# Sheet2.net
KiCad netlist of a schematic drawn in Altium Designer
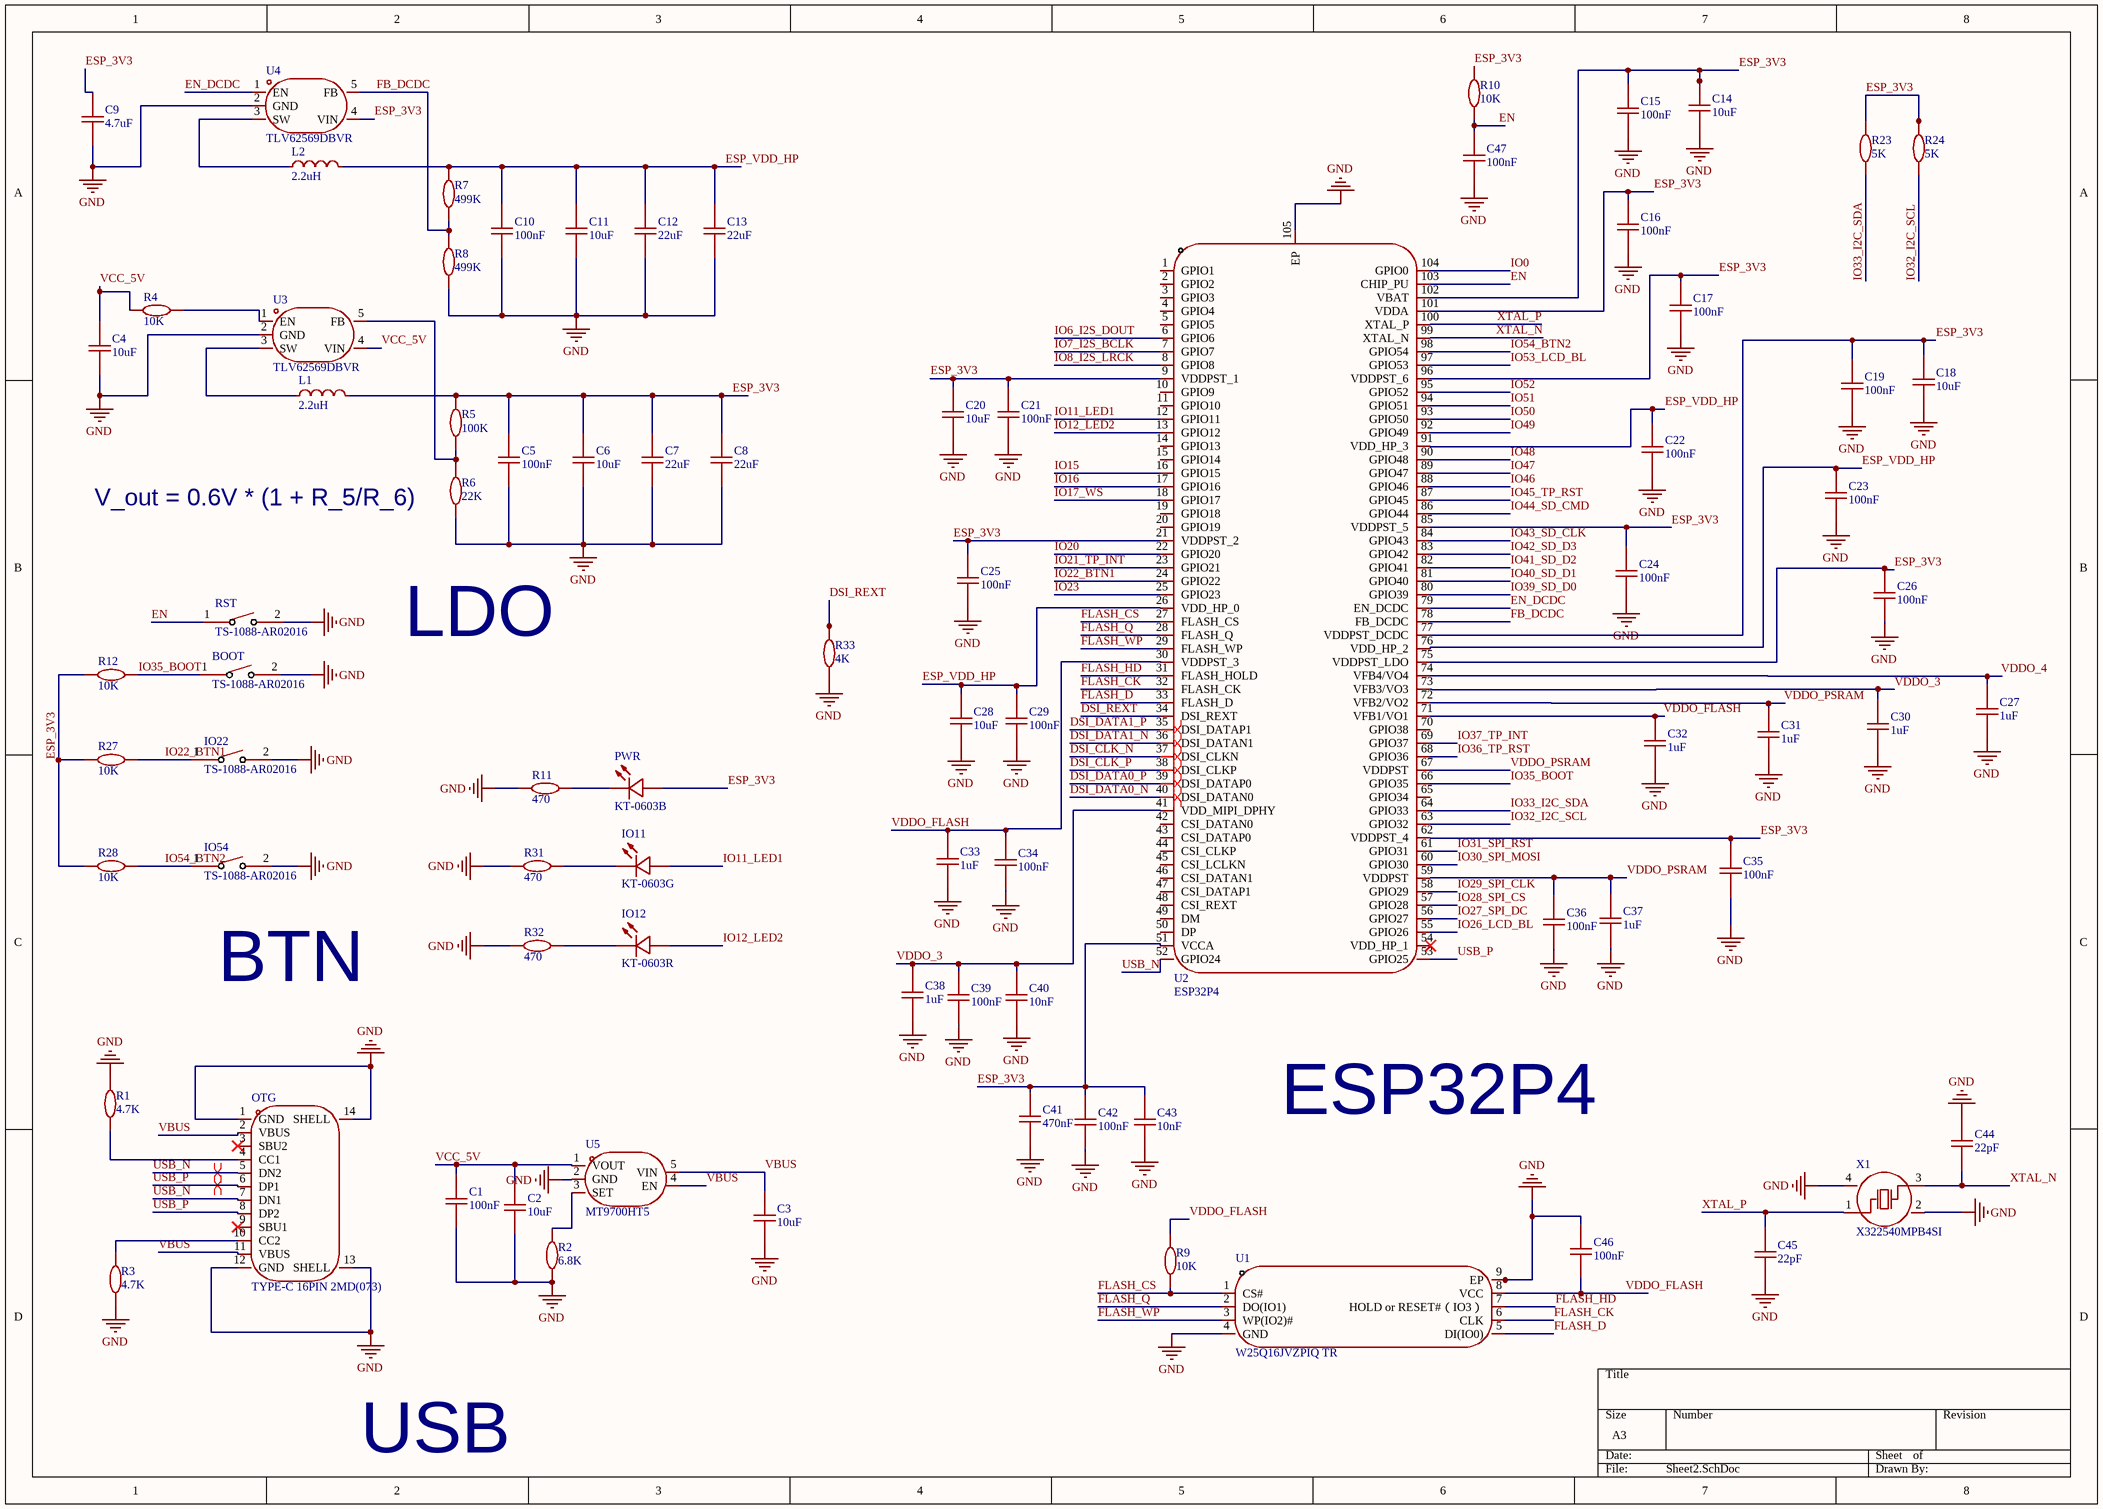
[diagram p0: Sheet2.SchDoc]

(export (version "E")
  (design (tool "Eeschema 10.0.6"))
  (components
    (comp (ref "BOOT")
      (value "TS-1088-AR02016")
      (footprint "SW-SMD_L3.9-W3.0-P4.45")
      (libsource (lib "Switch") (part "TS-1088-AR02016"))
    )
    (comp (ref "C1") (value "100nF") (footprint "C0402") (libsource (lib "RLC") (part "C0402")))
    (comp (ref "C2") (value "10uF") (footprint "C0603") (libsource (lib "RLC") (part "C0603")))
    (comp (ref "C3") (value "10uF") (footprint "C0603") (libsource (lib "RLC") (part "C0603")))
    (comp (ref "C4") (value "10uF") (footprint "C0603") (libsource (lib "RLC") (part "C0603")))
    (comp (ref "C5") (value "100nF") (footprint "C0402") (libsource (lib "RLC") (part "C0402")))
    (comp (ref "C6") (value "10uF") (footprint "C0603") (libsource (lib "RLC") (part "C0603")))
    (comp (ref "C7") (value "22uF") (footprint "C0603") (libsource (lib "RLC") (part "C0603")))
    (comp (ref "C8") (value "22uF") (footprint "C0603") (libsource (lib "RLC") (part "C0603")))
    (comp (ref "C9") (value "4.7uF") (footprint "C0603") (libsource (lib "RLC") (part "C0603")))
    (comp (ref "C10") (value "100nF") (footprint "C0402") (libsource (lib "RLC") (part "C0402")))
    (comp (ref "C11") (value "10uF") (footprint "C0603") (libsource (lib "RLC") (part "C0603")))
    (comp (ref "C12") (value "22uF") (footprint "C0603") (libsource (lib "RLC") (part "C0603")))
    (comp (ref "C13") (value "22uF") (footprint "C0603") (libsource (lib "RLC") (part "C0603")))
    (comp (ref "C14") (value "10uF") (footprint "C0603") (libsource (lib "RLC") (part "C0603")))
    (comp (ref "C15") (value "100nF") (footprint "C0402") (libsource (lib "RLC") (part "C0402")))
    (comp (ref "C16") (value "100nF") (footprint "C0402") (libsource (lib "RLC") (part "C0402")))
    (comp (ref "C17") (value "100nF") (footprint "C0402") (libsource (lib "RLC") (part "C0402")))
    (comp (ref "C18") (value "10uF") (footprint "C0603") (libsource (lib "RLC") (part "C0603")))
    (comp (ref "C19") (value "100nF") (footprint "C0402") (libsource (lib "RLC") (part "C0402")))
    (comp (ref "C20") (value "10uF") (footprint "C0603") (libsource (lib "RLC") (part "C0603")))
    (comp (ref "C21") (value "100nF") (footprint "C0402") (libsource (lib "RLC") (part "C0402")))
    (comp (ref "C22") (value "100nF") (footprint "C0402") (libsource (lib "RLC") (part "C0402")))
    (comp (ref "C23") (value "100nF") (footprint "C0402") (libsource (lib "RLC") (part "C0402")))
    (comp (ref "C24") (value "100nF") (footprint "C0402") (libsource (lib "RLC") (part "C0402")))
    (comp (ref "C25") (value "100nF") (footprint "C0402") (libsource (lib "RLC") (part "C0402")))
    (comp (ref "C26") (value "100nF") (footprint "C0402") (libsource (lib "RLC") (part "C0402")))
    (comp (ref "C27") (value "1uF") (footprint "C0402") (libsource (lib "RLC") (part "C0402")))
    (comp (ref "C28") (value "10uF") (footprint "C0603") (libsource (lib "RLC") (part "C0603")))
    (comp (ref "C29") (value "100nF") (footprint "C0402") (libsource (lib "RLC") (part "C0402")))
    (comp (ref "C30") (value "1uF") (footprint "C0402") (libsource (lib "RLC") (part "C0402")))
    (comp (ref "C31") (value "1uF") (footprint "C0402") (libsource (lib "RLC") (part "C0402")))
    (comp (ref "C32") (value "1uF") (footprint "C0402") (libsource (lib "RLC") (part "C0402")))
    (comp (ref "C33") (value "1uF") (footprint "C0402") (libsource (lib "RLC") (part "C0402")))
    (comp (ref "C34") (value "100nF") (footprint "C0402") (libsource (lib "RLC") (part "C0402")))
    (comp (ref "C35") (value "100nF") (footprint "C0402") (libsource (lib "RLC") (part "C0402")))
    (comp (ref "C36") (value "100nF") (footprint "C0402") (libsource (lib "RLC") (part "C0402")))
    (comp (ref "C37") (value "1uF") (footprint "C0402") (libsource (lib "RLC") (part "C0402")))
    (comp (ref "C38") (value "1uF") (footprint "C0402") (libsource (lib "RLC") (part "C0402")))
    (comp (ref "C39") (value "100nF") (footprint "C0402") (libsource (lib "RLC") (part "C0402")))
    (comp (ref "C40") (value "10nF") (footprint "C0402") (libsource (lib "RLC") (part "C0402")))
    (comp (ref "C41") (value "470nF") (footprint "C0402") (libsource (lib "RLC") (part "C0402")))
    (comp (ref "C42") (value "100nF") (footprint "C0402") (libsource (lib "RLC") (part "C0402")))
    (comp (ref "C43") (value "10nF") (footprint "C0402") (libsource (lib "RLC") (part "C0402")))
    (comp (ref "C44") (value "22pF") (footprint "C0402") (libsource (lib "RLC") (part "C0402")))
    (comp (ref "C45") (value "22pF") (footprint "C0402") (libsource (lib "RLC") (part "C0402")))
    (comp (ref "C46") (value "100nF") (footprint "C0402") (libsource (lib "RLC") (part "C0402")))
    (comp (ref "C47") (value "100nF") (footprint "C0402") (libsource (lib "RLC") (part "C0402")))
    (comp (ref "IO11") (value "KT-0603G") (footprint "LED0603-GR") (libsource (lib "LED") (part "KT-0603G")))
    (comp (ref "IO12") (value "KT-0603R") (footprint "LED0603-RD") (libsource (lib "LED") (part "KT-0603R")))
    (comp (ref "IO22")
      (value "TS-1088-AR02016")
      (footprint "SW-SMD_L3.9-W3.0-P4.45")
      (libsource (lib "Switch") (part "TS-1088-AR02016"))
    )
    (comp (ref "IO54")
      (value "TS-1088-AR02016")
      (footprint "SW-SMD_L3.9-W3.0-P4.45")
      (libsource (lib "Switch") (part "TS-1088-AR02016"))
    )
    (comp (ref "L1") (value "2.2uH") (footprint "L0402-SMD") (libsource (lib "RLC") (part "L0402-SMD")))
    (comp (ref "L2") (value "2.2uH") (footprint "L0402-SMD") (libsource (lib "RLC") (part "L0402-SMD")))
    (comp (ref "OTG")
      (value "TYPE-C 16PIN 2MD(073)")
      (footprint "USB-C-SMD_TYPE-C-6PIN-2MD-073")
      (libsource (lib "Connector") (part "TYPE-C 16PIN 2MD(073)"))
    )
    (comp (ref "PWR") (value "KT-0603B") (footprint "LED0603-BL") (libsource (lib "LED") (part "KT-0603B")))
    (comp (ref "R1") (value "4.7K") (footprint "R0402") (libsource (lib "RLC") (part "R0402")))
    (comp (ref "R2") (value "6.8K") (footprint "R0402") (libsource (lib "RLC") (part "R0402")))
    (comp (ref "R3") (value "4.7K") (footprint "R0402") (libsource (lib "RLC") (part "R0402")))
    (comp (ref "R4") (value "10K") (footprint "R0402") (libsource (lib "RLC") (part "R0402")))
    (comp (ref "R5") (value "100K") (footprint "R0402") (libsource (lib "RLC") (part "R0402")))
    (comp (ref "R6") (value "22K") (footprint "R0402") (libsource (lib "RLC") (part "R0402")))
    (comp (ref "R7") (value "499K") (footprint "R0402") (libsource (lib "RLC") (part "R0402")))
    (comp (ref "R8") (value "499K") (footprint "R0402") (libsource (lib "RLC") (part "R0402")))
    (comp (ref "R9") (value "10K") (footprint "R0402") (libsource (lib "RLC") (part "R0402")))
    (comp (ref "R10") (value "10K") (footprint "R0402") (libsource (lib "RLC") (part "R0402")))
    (comp (ref "R11") (value "470") (footprint "R0402") (libsource (lib "RLC") (part "R0402")))
    (comp (ref "R12") (value "10K") (footprint "R0402") (libsource (lib "RLC") (part "R0402")))
    (comp (ref "R23") (value "5K") (footprint "R0402") (libsource (lib "RLC") (part "R0402")))
    (comp (ref "R24") (value "5K") (footprint "R0402") (libsource (lib "RLC") (part "R0402")))
    (comp (ref "R27") (value "10K") (footprint "R0402") (libsource (lib "RLC") (part "R0402")))
    (comp (ref "R28") (value "10K") (footprint "R0402") (libsource (lib "RLC") (part "R0402")))
    (comp (ref "R31") (value "470") (footprint "R0402") (libsource (lib "RLC") (part "R0402")))
    (comp (ref "R32") (value "470") (footprint "R0402") (libsource (lib "RLC") (part "R0402")))
    (comp (ref "R33") (value "4K") (footprint "R0402") (libsource (lib "RLC") (part "R0402")))
    (comp (ref "RST")
      (value "TS-1088-AR02016")
      (footprint "SW-SMD_L3.9-W3.0-P4.45")
      (libsource (lib "Switch") (part "TS-1088-AR02016"))
    )
    (comp (ref "U1")
      (value "W25Q16JVZPIQ TR")
      (footprint "WSON-8_L6.0-W5.0-P1.27-BL-EP")
      (libsource (lib "IC") (part "W25Q16JVZPIQ TR"))
    )
    (comp (ref "U2")
      (value "ESP32P4")
      (footprint "QFN-104_L10.0-W10.0-P0.35-TL-EP7.5")
      (libsource (lib "IC") (part "ESP32P4"))
    )
    (comp (ref "U3")
      (value "TLV62569DBVR")
      (footprint "SOT-23-5_L3.0-W1.7-P0.95-LS2.8-BR")
      (libsource (lib "LDO") (part "TLV62569DBVR"))
    )
    (comp (ref "U4")
      (value "TLV62569DBVR")
      (footprint "SOT-23-5_L3.0-W1.7-P0.95-LS2.8-BR")
      (libsource (lib "LDO") (part "TLV62569DBVR"))
    )
    (comp (ref "U5")
      (value "MT9700HT5")
      (footprint "SOT-23-5_L3.0-W1.7-P0.95-LS2.8-BL")
      (libsource (lib "IC") (part "MT9700HT5"))
    )
    (comp (ref "X1")
      (value "X322540MPB4SI")
      (footprint "OSC-SMD_4P-L3.2-W2.5-BL_SIT8008BI")
      (libsource (lib "OSC") (part "X322540MPB4SI"))
    )
  )
  (nets
    (net (code "1") (name "/DSI_CLK_N") (class "Default")
      (node (ref "U2") (pin "37") (pinfunction "DSI_CLKN_37") (pintype "passive"))
    )
    (net (code "2") (name "/DSI_CLK_P") (class "Default")
      (node (ref "U2") (pin "38") (pinfunction "DSI_CLKP_38") (pintype "passive"))
    )
    (net (code "3") (name "/DSI_DATA0_N") (class "Default")
      (node (ref "U2") (pin "40") (pinfunction "DSI_DATAN0_40") (pintype "passive"))
    )
    (net (code "4") (name "/DSI_DATA0_P") (class "Default")
      (node (ref "U2") (pin "39") (pinfunction "DSI_DATAP0_39") (pintype "passive"))
    )
    (net (code "5") (name "/DSI_DATA1_N") (class "Default")
      (node (ref "U2") (pin "36") (pinfunction "DSI_DATAN1_36") (pintype "passive"))
    )
    (net (code "6") (name "/DSI_DATA1_P") (class "Default")
      (node (ref "U2") (pin "35") (pinfunction "DSI_DATAP1_35") (pintype "passive"))
    )
    (net (code "7") (name "/DSI_REXT") (class "Default")
      (node (ref "R33") (pin "1") (pinfunction "1_1") (pintype "passive"))
      (node (ref "U2") (pin "34") (pinfunction "DSI_REXT_34") (pintype "passive"))
    )
    (net (code "8") (name "/EN") (class "Default")
      (node (ref "C47") (pin "2") (pinfunction "2_2") (pintype "passive"))
      (node (ref "R10") (pin "1") (pinfunction "1_1") (pintype "passive"))
      (node (ref "RST") (pin "1") (pinfunction "1_1") (pintype "passive"))
      (node (ref "U2") (pin "103") (pinfunction "CHIP_PU_103") (pintype "passive"))
    )
    (net (code "9") (name "/EN_DCDC") (class "Default")
      (node (ref "U2") (pin "79") (pinfunction "EN_DCDC_79") (pintype "passive"))
      (node (ref "U4") (pin "1") (pinfunction "EN_1") (pintype "passive"))
    )
    (net (code "10") (name "/ESP_3V3") (class "Default")
      (node (ref "C14") (pin "2") (pinfunction "2_2") (pintype "passive"))
      (node (ref "C15") (pin "2") (pinfunction "2_2") (pintype "passive"))
      (node (ref "C16") (pin "2") (pinfunction "2_2") (pintype "passive"))
      (node (ref "C17") (pin "2") (pinfunction "2_2") (pintype "passive"))
      (node (ref "C18") (pin "2") (pinfunction "2_2") (pintype "passive"))
      (node (ref "C19") (pin "2") (pinfunction "2_2") (pintype "passive"))
      (node (ref "C20") (pin "2") (pinfunction "2_2") (pintype "passive"))
      (node (ref "C21") (pin "2") (pinfunction "2_2") (pintype "passive"))
      (node (ref "C24") (pin "2") (pinfunction "2_2") (pintype "passive"))
      (node (ref "C25") (pin "2") (pinfunction "2_2") (pintype "passive"))
      (node (ref "C26") (pin "2") (pinfunction "2_2") (pintype "passive"))
      (node (ref "C35") (pin "2") (pinfunction "2_2") (pintype "passive"))
      (node (ref "C41") (pin "2") (pinfunction "2_2") (pintype "passive"))
      (node (ref "C42") (pin "2") (pinfunction "2_2") (pintype "passive"))
      (node (ref "C43") (pin "2") (pinfunction "2_2") (pintype "passive"))
      (node (ref "C5") (pin "2") (pinfunction "2_2") (pintype "passive"))
      (node (ref "C6") (pin "2") (pinfunction "2_2") (pintype "passive"))
      (node (ref "C7") (pin "2") (pinfunction "2_2") (pintype "passive"))
      (node (ref "C8") (pin "2") (pinfunction "2_2") (pintype "passive"))
      (node (ref "C9") (pin "1") (pinfunction "1_1") (pintype "passive"))
      (node (ref "L1") (pin "2") (pinfunction "2_2") (pintype "passive"))
      (node (ref "PWR") (pin "2") (pinfunction "A_2") (pintype "passive"))
      (node (ref "R10") (pin "2") (pinfunction "2_2") (pintype "passive"))
      (node (ref "R12") (pin "2") (pinfunction "2_2") (pintype "passive"))
      (node (ref "R23") (pin "2") (pinfunction "2_2") (pintype "passive"))
      (node (ref "R24") (pin "2") (pinfunction "2_2") (pintype "passive"))
      (node (ref "R27") (pin "2") (pinfunction "2_2") (pintype "passive"))
      (node (ref "R28") (pin "2") (pinfunction "2_2") (pintype "passive"))
      (node (ref "R5") (pin "2") (pinfunction "2_2") (pintype "passive"))
      (node (ref "U2") (pin "101") (pinfunction "VDDA_101") (pintype "passive"))
      (node (ref "U2") (pin "102") (pinfunction "VBAT_102") (pintype "passive"))
      (node (ref "U2") (pin "21") (pinfunction "VDDPST_2_21") (pintype "passive"))
      (node (ref "U2") (pin "51") (pinfunction "VCCA_51") (pintype "passive"))
      (node (ref "U2") (pin "62") (pinfunction "VDDPST_4_62") (pintype "passive"))
      (node (ref "U2") (pin "75") (pinfunction "VDDPST_LDO_75") (pintype "passive"))
      (node (ref "U2") (pin "77") (pinfunction "VDDPST_DCDC_77") (pintype "passive"))
      (node (ref "U2") (pin "85") (pinfunction "VDDPST_5_85") (pintype "passive"))
      (node (ref "U2") (pin "9") (pinfunction "VDDPST_1_9") (pintype "passive"))
      (node (ref "U2") (pin "96") (pinfunction "VDDPST_6_96") (pintype "passive"))
      (node (ref "U4") (pin "4") (pinfunction "VIN_4") (pintype "passive"))
    )
    (net (code "11") (name "/ESP_VDD_HP") (class "Default")
      (node (ref "C10") (pin "2") (pinfunction "2_2") (pintype "passive"))
      (node (ref "C11") (pin "2") (pinfunction "2_2") (pintype "passive"))
      (node (ref "C12") (pin "2") (pinfunction "2_2") (pintype "passive"))
      (node (ref "C13") (pin "2") (pinfunction "2_2") (pintype "passive"))
      (node (ref "C22") (pin "2") (pinfunction "2_2") (pintype "passive"))
      (node (ref "C23") (pin "2") (pinfunction "2_2") (pintype "passive"))
      (node (ref "C28") (pin "2") (pinfunction "2_2") (pintype "passive"))
      (node (ref "C29") (pin "2") (pinfunction "2_2") (pintype "passive"))
      (node (ref "L2") (pin "2") (pinfunction "2_2") (pintype "passive"))
      (node (ref "R7") (pin "2") (pinfunction "2_2") (pintype "passive"))
      (node (ref "U2") (pin "26") (pinfunction "VDD_HP_0_26") (pintype "passive"))
      (node (ref "U2") (pin "76") (pinfunction "VDD_HP_2_76") (pintype "passive"))
      (node (ref "U2") (pin "91") (pinfunction "VDD_HP_3_91") (pintype "passive"))
    )
    (net (code "12") (name "/FB_DCDC") (class "Default")
      (node (ref "R7") (pin "1") (pinfunction "1_1") (pintype "passive"))
      (node (ref "R8") (pin "2") (pinfunction "2_2") (pintype "passive"))
      (node (ref "U2") (pin "78") (pinfunction "FB_DCDC_78") (pintype "passive"))
      (node (ref "U4") (pin "5") (pinfunction "FB_5") (pintype "passive"))
    )
    (net (code "13") (name "/FLASH_CK") (class "Default")
      (node (ref "U1") (pin "6") (pinfunction "CLK_6") (pintype "passive"))
      (node (ref "U2") (pin "32") (pinfunction "FLASH_CK_32") (pintype "passive"))
    )
    (net (code "14") (name "/FLASH_CS") (class "Default")
      (node (ref "R9") (pin "1") (pinfunction "1_1") (pintype "passive"))
      (node (ref "U1") (pin "1") (pinfunction "CS#_1") (pintype "passive"))
      (node (ref "U2") (pin "27") (pinfunction "FLASH_CS_27") (pintype "passive"))
    )
    (net (code "15") (name "/FLASH_D") (class "Default")
      (node (ref "U1") (pin "5") (pinfunction "DI(IO0)_5") (pintype "passive"))
      (node (ref "U2") (pin "33") (pinfunction "FLASH_D_33") (pintype "passive"))
    )
    (net (code "16") (name "/FLASH_HD") (class "Default")
      (node (ref "U1") (pin "7") (pinfunction "HOLD_or_RESET#（IO3）_7") (pintype "passive"))
      (node (ref "U2") (pin "31") (pinfunction "FLASH_HOLD_31") (pintype "passive"))
    )
    (net (code "17") (name "/FLASH_Q") (class "Default")
      (node (ref "U1") (pin "2") (pinfunction "DO(IO1)_2") (pintype "passive"))
      (node (ref "U2") (pin "28") (pinfunction "FLASH_Q_28") (pintype "passive"))
    )
    (net (code "18") (name "/FLASH_WP") (class "Default")
      (node (ref "U1") (pin "3") (pinfunction "WP(IO2)#_3") (pintype "passive"))
      (node (ref "U2") (pin "29") (pinfunction "FLASH_WP_29") (pintype "passive"))
    )
    (net (code "19") (name "/IO0") (class "Default")
      (node (ref "U2") (pin "104") (pinfunction "GPIO0_104") (pintype "passive"))
    )
    (net (code "20") (name "/IO6_I2S_DOUT") (class "Default")
      (node (ref "U2") (pin "6") (pinfunction "GPIO6_6") (pintype "passive"))
    )
    (net (code "21") (name "/IO7_I2S_BCLK") (class "Default")
      (node (ref "U2") (pin "7") (pinfunction "GPIO7_7") (pintype "passive"))
    )
    (net (code "22") (name "/IO8_I2S_LRCK") (class "Default")
      (node (ref "U2") (pin "8") (pinfunction "GPIO8_8") (pintype "passive"))
    )
    (net (code "23") (name "/IO11_LED1") (class "Default")
      (node (ref "IO11") (pin "2") (pinfunction "A_2") (pintype "passive"))
      (node (ref "U2") (pin "12") (pinfunction "GPIO11_12") (pintype "passive"))
    )
    (net (code "24") (name "/IO12_LED2") (class "Default")
      (node (ref "IO12") (pin "2") (pinfunction "A_2") (pintype "passive"))
      (node (ref "U2") (pin "13") (pinfunction "GPIO12_13") (pintype "passive"))
    )
    (net (code "25") (name "/IO15") (class "Default")
      (node (ref "U2") (pin "16") (pinfunction "GPIO15_16") (pintype "passive"))
    )
    (net (code "26") (name "/IO16") (class "Default")
      (node (ref "U2") (pin "17") (pinfunction "GPIO16_17") (pintype "passive"))
    )
    (net (code "27") (name "/IO17_WS") (class "Default")
      (node (ref "U2") (pin "18") (pinfunction "GPIO17_18") (pintype "passive"))
    )
    (net (code "28") (name "/IO20") (class "Default")
      (node (ref "U2") (pin "22") (pinfunction "GPIO20_22") (pintype "passive"))
    )
    (net (code "29") (name "/IO21_TP_INT") (class "Default")
      (node (ref "U2") (pin "23") (pinfunction "GPIO21_23") (pintype "passive"))
    )
    (net (code "30") (name "/IO22_BTN1") (class "Default")
      (node (ref "IO22") (pin "1") (pinfunction "1_1") (pintype "passive"))
      (node (ref "R27") (pin "1") (pinfunction "1_1") (pintype "passive"))
      (node (ref "U2") (pin "24") (pinfunction "GPIO22_24") (pintype "passive"))
    )
    (net (code "31") (name "/IO23") (class "Default")
      (node (ref "U2") (pin "25") (pinfunction "GPIO23_25") (pintype "passive"))
    )
    (net (code "32") (name "/IO26_LCD_BL") (class "Default")
      (node (ref "U2") (pin "55") (pinfunction "GPIO26_55") (pintype "passive"))
    )
    (net (code "33") (name "/IO27_SPI_DC") (class "Default")
      (node (ref "U2") (pin "56") (pinfunction "GPIO27_56") (pintype "passive"))
    )
    (net (code "34") (name "/IO28_SPI_CS") (class "Default")
      (node (ref "U2") (pin "57") (pinfunction "GPIO28_57") (pintype "passive"))
    )
    (net (code "35") (name "/IO29_SPI_CLK") (class "Default")
      (node (ref "U2") (pin "58") (pinfunction "GPIO29_58") (pintype "passive"))
    )
    (net (code "36") (name "/IO30_SPI_MOSI") (class "Default")
      (node (ref "U2") (pin "60") (pinfunction "GPIO30_60") (pintype "passive"))
    )
    (net (code "37") (name "/IO31_SPI_RST") (class "Default")
      (node (ref "U2") (pin "61") (pinfunction "GPIO31_61") (pintype "passive"))
    )
    (net (code "38") (name "/IO32_I2C_SCL") (class "Default")
      (node (ref "R24") (pin "1") (pinfunction "1_1") (pintype "passive"))
      (node (ref "U2") (pin "63") (pinfunction "GPIO32_63") (pintype "passive"))
    )
    (net (code "39") (name "/IO33_I2C_SDA") (class "Default")
      (node (ref "R23") (pin "1") (pinfunction "1_1") (pintype "passive"))
      (node (ref "U2") (pin "64") (pinfunction "GPIO33_64") (pintype "passive"))
    )
    (net (code "40") (name "/IO35_BOOT") (class "Default")
      (node (ref "BOOT") (pin "1") (pinfunction "1_1") (pintype "passive"))
      (node (ref "R12") (pin "1") (pinfunction "1_1") (pintype "passive"))
      (node (ref "U2") (pin "66") (pinfunction "GPIO35_66") (pintype "passive"))
    )
    (net (code "41") (name "/IO36_TP_RST") (class "Default")
      (node (ref "U2") (pin "68") (pinfunction "GPIO36_68") (pintype "passive"))
    )
    (net (code "42") (name "/IO37_TP_INT") (class "Default")
      (node (ref "U2") (pin "69") (pinfunction "GPIO37_69") (pintype "passive"))
    )
    (net (code "43") (name "/IO39_SD_D0") (class "Default")
      (node (ref "U2") (pin "80") (pinfunction "GPIO39_80") (pintype "passive"))
    )
    (net (code "44") (name "/IO40_SD_D1") (class "Default")
      (node (ref "U2") (pin "81") (pinfunction "GPIO40_81") (pintype "passive"))
    )
    (net (code "45") (name "/IO41_SD_D2") (class "Default")
      (node (ref "U2") (pin "82") (pinfunction "GPIO41_82") (pintype "passive"))
    )
    (net (code "46") (name "/IO42_SD_D3") (class "Default")
      (node (ref "U2") (pin "83") (pinfunction "GPIO42_83") (pintype "passive"))
    )
    (net (code "47") (name "/IO43_SD_CLK") (class "Default")
      (node (ref "U2") (pin "84") (pinfunction "GPIO43_84") (pintype "passive"))
    )
    (net (code "48") (name "/IO44_SD_CMD") (class "Default")
      (node (ref "U2") (pin "86") (pinfunction "GPIO44_86") (pintype "passive"))
    )
    (net (code "49") (name "/IO45_TP_RST") (class "Default")
      (node (ref "U2") (pin "87") (pinfunction "GPIO45_87") (pintype "passive"))
    )
    (net (code "50") (name "/IO46") (class "Default")
      (node (ref "U2") (pin "88") (pinfunction "GPIO46_88") (pintype "passive"))
    )
    (net (code "51") (name "/IO47") (class "Default")
      (node (ref "U2") (pin "89") (pinfunction "GPIO47_89") (pintype "passive"))
    )
    (net (code "52") (name "/IO48") (class "Default")
      (node (ref "U2") (pin "90") (pinfunction "GPIO48_90") (pintype "passive"))
    )
    (net (code "53") (name "/IO49") (class "Default")
      (node (ref "U2") (pin "92") (pinfunction "GPIO49_92") (pintype "passive"))
    )
    (net (code "54") (name "/IO50") (class "Default")
      (node (ref "U2") (pin "93") (pinfunction "GPIO50_93") (pintype "passive"))
    )
    (net (code "55") (name "/IO51") (class "Default")
      (node (ref "U2") (pin "94") (pinfunction "GPIO51_94") (pintype "passive"))
    )
    (net (code "56") (name "/IO52") (class "Default")
      (node (ref "U2") (pin "95") (pinfunction "GPIO52_95") (pintype "passive"))
    )
    (net (code "57") (name "/IO53_LCD_BL") (class "Default")
      (node (ref "U2") (pin "97") (pinfunction "GPIO53_97") (pintype "passive"))
    )
    (net (code "58") (name "/IO54_BTN2") (class "Default")
      (node (ref "IO54") (pin "1") (pinfunction "1_1") (pintype "passive"))
      (node (ref "R28") (pin "1") (pinfunction "1_1") (pintype "passive"))
      (node (ref "U2") (pin "98") (pinfunction "GPIO54_98") (pintype "passive"))
    )
    (net (code "59") (name "/USB_N") (class "Default")
      (node (ref "OTG") (pin "5") (pinfunction "DN2_5") (pintype "passive"))
      (node (ref "OTG") (pin "7") (pinfunction "DN1_7") (pintype "passive"))
      (node (ref "U2") (pin "52") (pinfunction "GPIO24_52") (pintype "passive"))
    )
    (net (code "60") (name "/USB_P") (class "Default")
      (node (ref "OTG") (pin "6") (pinfunction "DP1_6") (pintype "passive"))
      (node (ref "OTG") (pin "8") (pinfunction "DP2_8") (pintype "passive"))
      (node (ref "U2") (pin "53") (pinfunction "GPIO25_53") (pintype "passive"))
    )
    (net (code "61") (name "/VBUS") (class "Default")
      (node (ref "C3") (pin "1") (pinfunction "1_1") (pintype "passive"))
      (node (ref "OTG") (pin "11") (pinfunction "VBUS_11") (pintype "passive"))
      (node (ref "OTG") (pin "2") (pinfunction "VBUS_2") (pintype "passive"))
      (node (ref "U5") (pin "4") (pinfunction "EN_4") (pintype "passive"))
      (node (ref "U5") (pin "5") (pinfunction "VIN_5") (pintype "passive"))
    )
    (net (code "62") (name "/VCC_5V") (class "Default")
      (node (ref "C1") (pin "2") (pinfunction "2_2") (pintype "passive"))
      (node (ref "C2") (pin "1") (pinfunction "1_1") (pintype "passive"))
      (node (ref "C4") (pin "1") (pinfunction "1_1") (pintype "passive"))
      (node (ref "R4") (pin "2") (pinfunction "2_2") (pintype "passive"))
      (node (ref "U3") (pin "4") (pinfunction "VIN_4") (pintype "passive"))
      (node (ref "U5") (pin "1") (pinfunction "VOUT_1") (pintype "passive"))
    )
    (net (code "63") (name "/VDDO_3") (class "Default")
      (node (ref "C30") (pin "2") (pinfunction "2_2") (pintype "passive"))
      (node (ref "C38") (pin "2") (pinfunction "2_2") (pintype "passive"))
      (node (ref "C39") (pin "2") (pinfunction "2_2") (pintype "passive"))
      (node (ref "C40") (pin "2") (pinfunction "2_2") (pintype "passive"))
      (node (ref "U2") (pin "41") (pinfunction "VDD_MIPI_DPHY_41") (pintype "passive"))
      (node (ref "U2") (pin "73") (pinfunction "VFB3/VO3_73") (pintype "passive"))
    )
    (net (code "64") (name "/VDDO_4") (class "Default")
      (node (ref "C27") (pin "2") (pinfunction "2_2") (pintype "passive"))
      (node (ref "U2") (pin "74") (pinfunction "VFB4/VO4_74") (pintype "passive"))
    )
    (net (code "65") (name "/VDDO_FLASH") (class "Default")
      (node (ref "C32") (pin "2") (pinfunction "2_2") (pintype "passive"))
      (node (ref "C33") (pin "2") (pinfunction "2_2") (pintype "passive"))
      (node (ref "C34") (pin "2") (pinfunction "2_2") (pintype "passive"))
      (node (ref "C46") (pin "1") (pinfunction "1_1") (pintype "passive"))
      (node (ref "R9") (pin "2") (pinfunction "2_2") (pintype "passive"))
      (node (ref "U1") (pin "8") (pinfunction "VCC_8") (pintype "passive"))
      (node (ref "U2") (pin "30") (pinfunction "VDDPST_3_30") (pintype "passive"))
      (node (ref "U2") (pin "71") (pinfunction "VFB1/VO1_71") (pintype "passive"))
    )
    (net (code "66") (name "/VDDO_PSRAM") (class "Default")
      (node (ref "C31") (pin "2") (pinfunction "2_2") (pintype "passive"))
      (node (ref "C36") (pin "2") (pinfunction "2_2") (pintype "passive"))
      (node (ref "C37") (pin "2") (pinfunction "2_2") (pintype "passive"))
      (node (ref "U2") (pin "59") (pinfunction "VDDPST_59") (pintype "passive"))
      (node (ref "U2") (pin "67") (pinfunction "VDDPST_67") (pintype "passive"))
      (node (ref "U2") (pin "72") (pinfunction "VFB2/VO2_72") (pintype "passive"))
    )
    (net (code "67") (name "/XTAL_N") (class "Default")
      (node (ref "C44") (pin "1") (pinfunction "1_1") (pintype "passive"))
      (node (ref "U2") (pin "99") (pinfunction "XTAL_N_99") (pintype "passive"))
      (node (ref "X1") (pin "3") (pinfunction "OSC2_3") (pintype "passive"))
    )
    (net (code "68") (name "/XTAL_P") (class "Default")
      (node (ref "C45") (pin "2") (pinfunction "2_2") (pintype "passive"))
      (node (ref "U2") (pin "100") (pinfunction "XTAL_P_100") (pintype "passive"))
      (node (ref "X1") (pin "1") (pinfunction "OSC1_1") (pintype "passive"))
    )
    (net (code "69") (name "GND") (class "Default")
      (node (ref "BOOT") (pin "2") (pinfunction "2_2") (pintype "passive"))
      (node (ref "C1") (pin "1") (pinfunction "1_1") (pintype "passive"))
      (node (ref "C10") (pin "1") (pinfunction "1_1") (pintype "passive"))
      (node (ref "C11") (pin "1") (pinfunction "1_1") (pintype "passive"))
      (node (ref "C12") (pin "1") (pinfunction "1_1") (pintype "passive"))
      (node (ref "C13") (pin "1") (pinfunction "1_1") (pintype "passive"))
      (node (ref "C14") (pin "1") (pinfunction "1_1") (pintype "passive"))
      (node (ref "C15") (pin "1") (pinfunction "1_1") (pintype "passive"))
      (node (ref "C16") (pin "1") (pinfunction "1_1") (pintype "passive"))
      (node (ref "C17") (pin "1") (pinfunction "1_1") (pintype "passive"))
      (node (ref "C18") (pin "1") (pinfunction "1_1") (pintype "passive"))
      (node (ref "C19") (pin "1") (pinfunction "1_1") (pintype "passive"))
      (node (ref "C2") (pin "2") (pinfunction "2_2") (pintype "passive"))
      (node (ref "C20") (pin "1") (pinfunction "1_1") (pintype "passive"))
      (node (ref "C21") (pin "1") (pinfunction "1_1") (pintype "passive"))
      (node (ref "C22") (pin "1") (pinfunction "1_1") (pintype "passive"))
      (node (ref "C23") (pin "1") (pinfunction "1_1") (pintype "passive"))
      (node (ref "C24") (pin "1") (pinfunction "1_1") (pintype "passive"))
      (node (ref "C25") (pin "1") (pinfunction "1_1") (pintype "passive"))
      (node (ref "C26") (pin "1") (pinfunction "1_1") (pintype "passive"))
      (node (ref "C27") (pin "1") (pinfunction "1_1") (pintype "passive"))
      (node (ref "C28") (pin "1") (pinfunction "1_1") (pintype "passive"))
      (node (ref "C29") (pin "1") (pinfunction "1_1") (pintype "passive"))
      (node (ref "C3") (pin "2") (pinfunction "2_2") (pintype "passive"))
      (node (ref "C30") (pin "1") (pinfunction "1_1") (pintype "passive"))
      (node (ref "C31") (pin "1") (pinfunction "1_1") (pintype "passive"))
      (node (ref "C32") (pin "1") (pinfunction "1_1") (pintype "passive"))
      (node (ref "C33") (pin "1") (pinfunction "1_1") (pintype "passive"))
      (node (ref "C34") (pin "1") (pinfunction "1_1") (pintype "passive"))
      (node (ref "C35") (pin "1") (pinfunction "1_1") (pintype "passive"))
      (node (ref "C36") (pin "1") (pinfunction "1_1") (pintype "passive"))
      (node (ref "C37") (pin "1") (pinfunction "1_1") (pintype "passive"))
      (node (ref "C38") (pin "1") (pinfunction "1_1") (pintype "passive"))
      (node (ref "C39") (pin "1") (pinfunction "1_1") (pintype "passive"))
      (node (ref "C4") (pin "2") (pinfunction "2_2") (pintype "passive"))
      (node (ref "C40") (pin "1") (pinfunction "1_1") (pintype "passive"))
      (node (ref "C41") (pin "1") (pinfunction "1_1") (pintype "passive"))
      (node (ref "C42") (pin "1") (pinfunction "1_1") (pintype "passive"))
      (node (ref "C43") (pin "1") (pinfunction "1_1") (pintype "passive"))
      (node (ref "C44") (pin "2") (pinfunction "2_2") (pintype "passive"))
      (node (ref "C45") (pin "1") (pinfunction "1_1") (pintype "passive"))
      (node (ref "C46") (pin "2") (pinfunction "2_2") (pintype "passive"))
      (node (ref "C47") (pin "1") (pinfunction "1_1") (pintype "passive"))
      (node (ref "C5") (pin "1") (pinfunction "1_1") (pintype "passive"))
      (node (ref "C6") (pin "1") (pinfunction "1_1") (pintype "passive"))
      (node (ref "C7") (pin "1") (pinfunction "1_1") (pintype "passive"))
      (node (ref "C8") (pin "1") (pinfunction "1_1") (pintype "passive"))
      (node (ref "C9") (pin "2") (pinfunction "2_2") (pintype "passive"))
      (node (ref "IO22") (pin "2") (pinfunction "2_2") (pintype "passive"))
      (node (ref "IO54") (pin "2") (pinfunction "2_2") (pintype "passive"))
      (node (ref "OTG") (pin "1") (pinfunction "GND_1") (pintype "passive"))
      (node (ref "OTG") (pin "12") (pinfunction "GND_12") (pintype "passive"))
      (node (ref "OTG") (pin "13") (pinfunction "SHELL_13") (pintype "passive"))
      (node (ref "OTG") (pin "14") (pinfunction "SHELL_14") (pintype "passive"))
      (node (ref "R1") (pin "2") (pinfunction "2_2") (pintype "passive"))
      (node (ref "R11") (pin "2") (pinfunction "2_2") (pintype "passive"))
      (node (ref "R2") (pin "2") (pinfunction "2_2") (pintype "passive"))
      (node (ref "R3") (pin "1") (pinfunction "1_1") (pintype "passive"))
      (node (ref "R31") (pin "2") (pinfunction "2_2") (pintype "passive"))
      (node (ref "R32") (pin "2") (pinfunction "2_2") (pintype "passive"))
      (node (ref "R33") (pin "2") (pinfunction "2_2") (pintype "passive"))
      (node (ref "R6") (pin "1") (pinfunction "1_1") (pintype "passive"))
      (node (ref "R8") (pin "1") (pinfunction "1_1") (pintype "passive"))
      (node (ref "RST") (pin "2") (pinfunction "2_2") (pintype "passive"))
      (node (ref "U1") (pin "4") (pinfunction "GND_4") (pintype "passive"))
      (node (ref "U1") (pin "9") (pinfunction "EP_9") (pintype "passive"))
      (node (ref "U2") (pin "105") (pinfunction "EP_105") (pintype "passive"))
      (node (ref "U3") (pin "2") (pinfunction "GND_2") (pintype "passive"))
      (node (ref "U4") (pin "2") (pinfunction "GND_2") (pintype "passive"))
      (node (ref "U5") (pin "2") (pinfunction "GND_2") (pintype "passive"))
      (node (ref "X1") (pin "2") (pinfunction "GND_2") (pintype "passive"))
      (node (ref "X1") (pin "4") (pinfunction "GND_4") (pintype "passive"))
    )
    (net (code "70") (name "Net-(IO11-K)") (class "Default")
      (node (ref "IO11") (pin "1") (pinfunction "K_1") (pintype "passive"))
      (node (ref "R31") (pin "1") (pinfunction "1_1") (pintype "passive"))
    )
    (net (code "71") (name "Net-(IO12-K)") (class "Default")
      (node (ref "IO12") (pin "1") (pinfunction "K_1") (pintype "passive"))
      (node (ref "R32") (pin "1") (pinfunction "1_1") (pintype "passive"))
    )
    (net (code "72") (name "Net-(OTG-CC1)") (class "Default")
      (node (ref "OTG") (pin "4") (pinfunction "CC1_4") (pintype "passive"))
      (node (ref "R1") (pin "1") (pinfunction "1_1") (pintype "passive"))
    )
    (net (code "73") (name "Net-(OTG-CC2)") (class "Default")
      (node (ref "OTG") (pin "10") (pinfunction "CC2_10") (pintype "passive"))
      (node (ref "R3") (pin "2") (pinfunction "2_2") (pintype "passive"))
    )
    (net (code "74") (name "Net-(PWR-K)") (class "Default")
      (node (ref "PWR") (pin "1") (pinfunction "K_1") (pintype "passive"))
      (node (ref "R11") (pin "1") (pinfunction "1_1") (pintype "passive"))
    )
    (net (code "75") (name "Net-(U3-EN)") (class "Default")
      (node (ref "R4") (pin "1") (pinfunction "1_1") (pintype "passive"))
      (node (ref "U3") (pin "1") (pinfunction "EN_1") (pintype "passive"))
    )
    (net (code "76") (name "Net-(U3-FB)") (class "Default")
      (node (ref "R5") (pin "1") (pinfunction "1_1") (pintype "passive"))
      (node (ref "R6") (pin "2") (pinfunction "2_2") (pintype "passive"))
      (node (ref "U3") (pin "5") (pinfunction "FB_5") (pintype "passive"))
    )
    (net (code "77") (name "Net-(U3-SW)") (class "Default")
      (node (ref "L1") (pin "1") (pinfunction "1_1") (pintype "passive"))
      (node (ref "U3") (pin "3") (pinfunction "SW_3") (pintype "passive"))
    )
    (net (code "78") (name "Net-(U4-SW)") (class "Default")
      (node (ref "L2") (pin "1") (pinfunction "1_1") (pintype "passive"))
      (node (ref "U4") (pin "3") (pinfunction "SW_3") (pintype "passive"))
    )
    (net (code "79") (name "Net-(U5-SET)") (class "Default")
      (node (ref "R2") (pin "1") (pinfunction "1_1") (pintype "passive"))
      (node (ref "U5") (pin "3") (pinfunction "SET_3") (pintype "passive"))
    )
    (net (code "80") (name "unconnected-(OTG-SBU1-Pad9)") (class "Default")
      (node (ref "OTG") (pin "9") (pinfunction "SBU1_9") (pintype "passive+no_connect"))
    )
    (net (code "81") (name "unconnected-(OTG-SBU2-Pad3)") (class "Default")
      (node (ref "OTG") (pin "3") (pinfunction "SBU2_3") (pintype "passive+no_connect"))
    )
    (net (code "82") (name "unconnected-(U2-CSI_CLKP-Pad44)") (class "Default")
      (node (ref "U2") (pin "44") (pinfunction "CSI_CLKP_44") (pintype "passive"))
    )
    (net (code "83") (name "unconnected-(U2-CSI_DATAN0-Pad42)") (class "Default")
      (node (ref "U2") (pin "42") (pinfunction "CSI_DATAN0_42") (pintype "passive"))
    )
    (net (code "84") (name "unconnected-(U2-CSI_DATAN1-Pad46)") (class "Default")
      (node (ref "U2") (pin "46") (pinfunction "CSI_DATAN1_46") (pintype "passive"))
    )
    (net (code "85") (name "unconnected-(U2-CSI_DATAP0-Pad43)") (class "Default")
      (node (ref "U2") (pin "43") (pinfunction "CSI_DATAP0_43") (pintype "passive"))
    )
    (net (code "86") (name "unconnected-(U2-CSI_DATAP1-Pad47)") (class "Default")
      (node (ref "U2") (pin "47") (pinfunction "CSI_DATAP1_47") (pintype "passive"))
    )
    (net (code "87") (name "unconnected-(U2-CSI_LCLKN-Pad45)") (class "Default")
      (node (ref "U2") (pin "45") (pinfunction "CSI_LCLKN_45") (pintype "passive"))
    )
    (net (code "88") (name "unconnected-(U2-CSI_REXT-Pad48)") (class "Default")
      (node (ref "U2") (pin "48") (pinfunction "CSI_REXT_48") (pintype "passive"))
    )
    (net (code "89") (name "unconnected-(U2-DM-Pad49)") (class "Default")
      (node (ref "U2") (pin "49") (pinfunction "DM_49") (pintype "passive"))
    )
    (net (code "90") (name "unconnected-(U2-DP-Pad50)") (class "Default")
      (node (ref "U2") (pin "50") (pinfunction "DP_50") (pintype "passive"))
    )
    (net (code "91") (name "unconnected-(U2-GPIO1-Pad1)") (class "Default")
      (node (ref "U2") (pin "1") (pinfunction "GPIO1_1") (pintype "passive"))
    )
    (net (code "92") (name "unconnected-(U2-GPIO2-Pad2)") (class "Default")
      (node (ref "U2") (pin "2") (pinfunction "GPIO2_2") (pintype "passive"))
    )
    (net (code "93") (name "unconnected-(U2-GPIO3-Pad3)") (class "Default")
      (node (ref "U2") (pin "3") (pinfunction "GPIO3_3") (pintype "passive"))
    )
    (net (code "94") (name "unconnected-(U2-GPIO4-Pad4)") (class "Default")
      (node (ref "U2") (pin "4") (pinfunction "GPIO4_4") (pintype "passive"))
    )
    (net (code "95") (name "unconnected-(U2-GPIO5-Pad5)") (class "Default")
      (node (ref "U2") (pin "5") (pinfunction "GPIO5_5") (pintype "passive"))
    )
    (net (code "96") (name "unconnected-(U2-GPIO9-Pad10)") (class "Default")
      (node (ref "U2") (pin "10") (pinfunction "GPIO9_10") (pintype "passive"))
    )
    (net (code "97") (name "unconnected-(U2-GPIO10-Pad11)") (class "Default")
      (node (ref "U2") (pin "11") (pinfunction "GPIO10_11") (pintype "passive"))
    )
    (net (code "98") (name "unconnected-(U2-GPIO13-Pad14)") (class "Default")
      (node (ref "U2") (pin "14") (pinfunction "GPIO13_14") (pintype "passive"))
    )
    (net (code "99") (name "unconnected-(U2-GPIO14-Pad15)") (class "Default")
      (node (ref "U2") (pin "15") (pinfunction "GPIO14_15") (pintype "passive"))
    )
    (net (code "100") (name "unconnected-(U2-GPIO18-Pad19)") (class "Default")
      (node (ref "U2") (pin "19") (pinfunction "GPIO18_19") (pintype "passive"))
    )
    (net (code "101") (name "unconnected-(U2-GPIO19-Pad20)") (class "Default")
      (node (ref "U2") (pin "20") (pinfunction "GPIO19_20") (pintype "passive"))
    )
    (net (code "102") (name "unconnected-(U2-GPIO34-Pad65)") (class "Default")
      (node (ref "U2") (pin "65") (pinfunction "GPIO34_65") (pintype "passive"))
    )
    (net (code "103") (name "unconnected-(U2-GPIO38-Pad70)") (class "Default")
      (node (ref "U2") (pin "70") (pinfunction "GPIO38_70") (pintype "passive"))
    )
    (net (code "104") (name "unconnected-(U2-VDD_HP_1-Pad54)") (class "Default")
      (node (ref "U2") (pin "54") (pinfunction "VDD_HP_1_54") (pintype "passive+no_connect"))
    )
  )
)
